# loadCell_Amplifier_v0_01.net
KiCad netlist of a schematic drawn in EAGLE
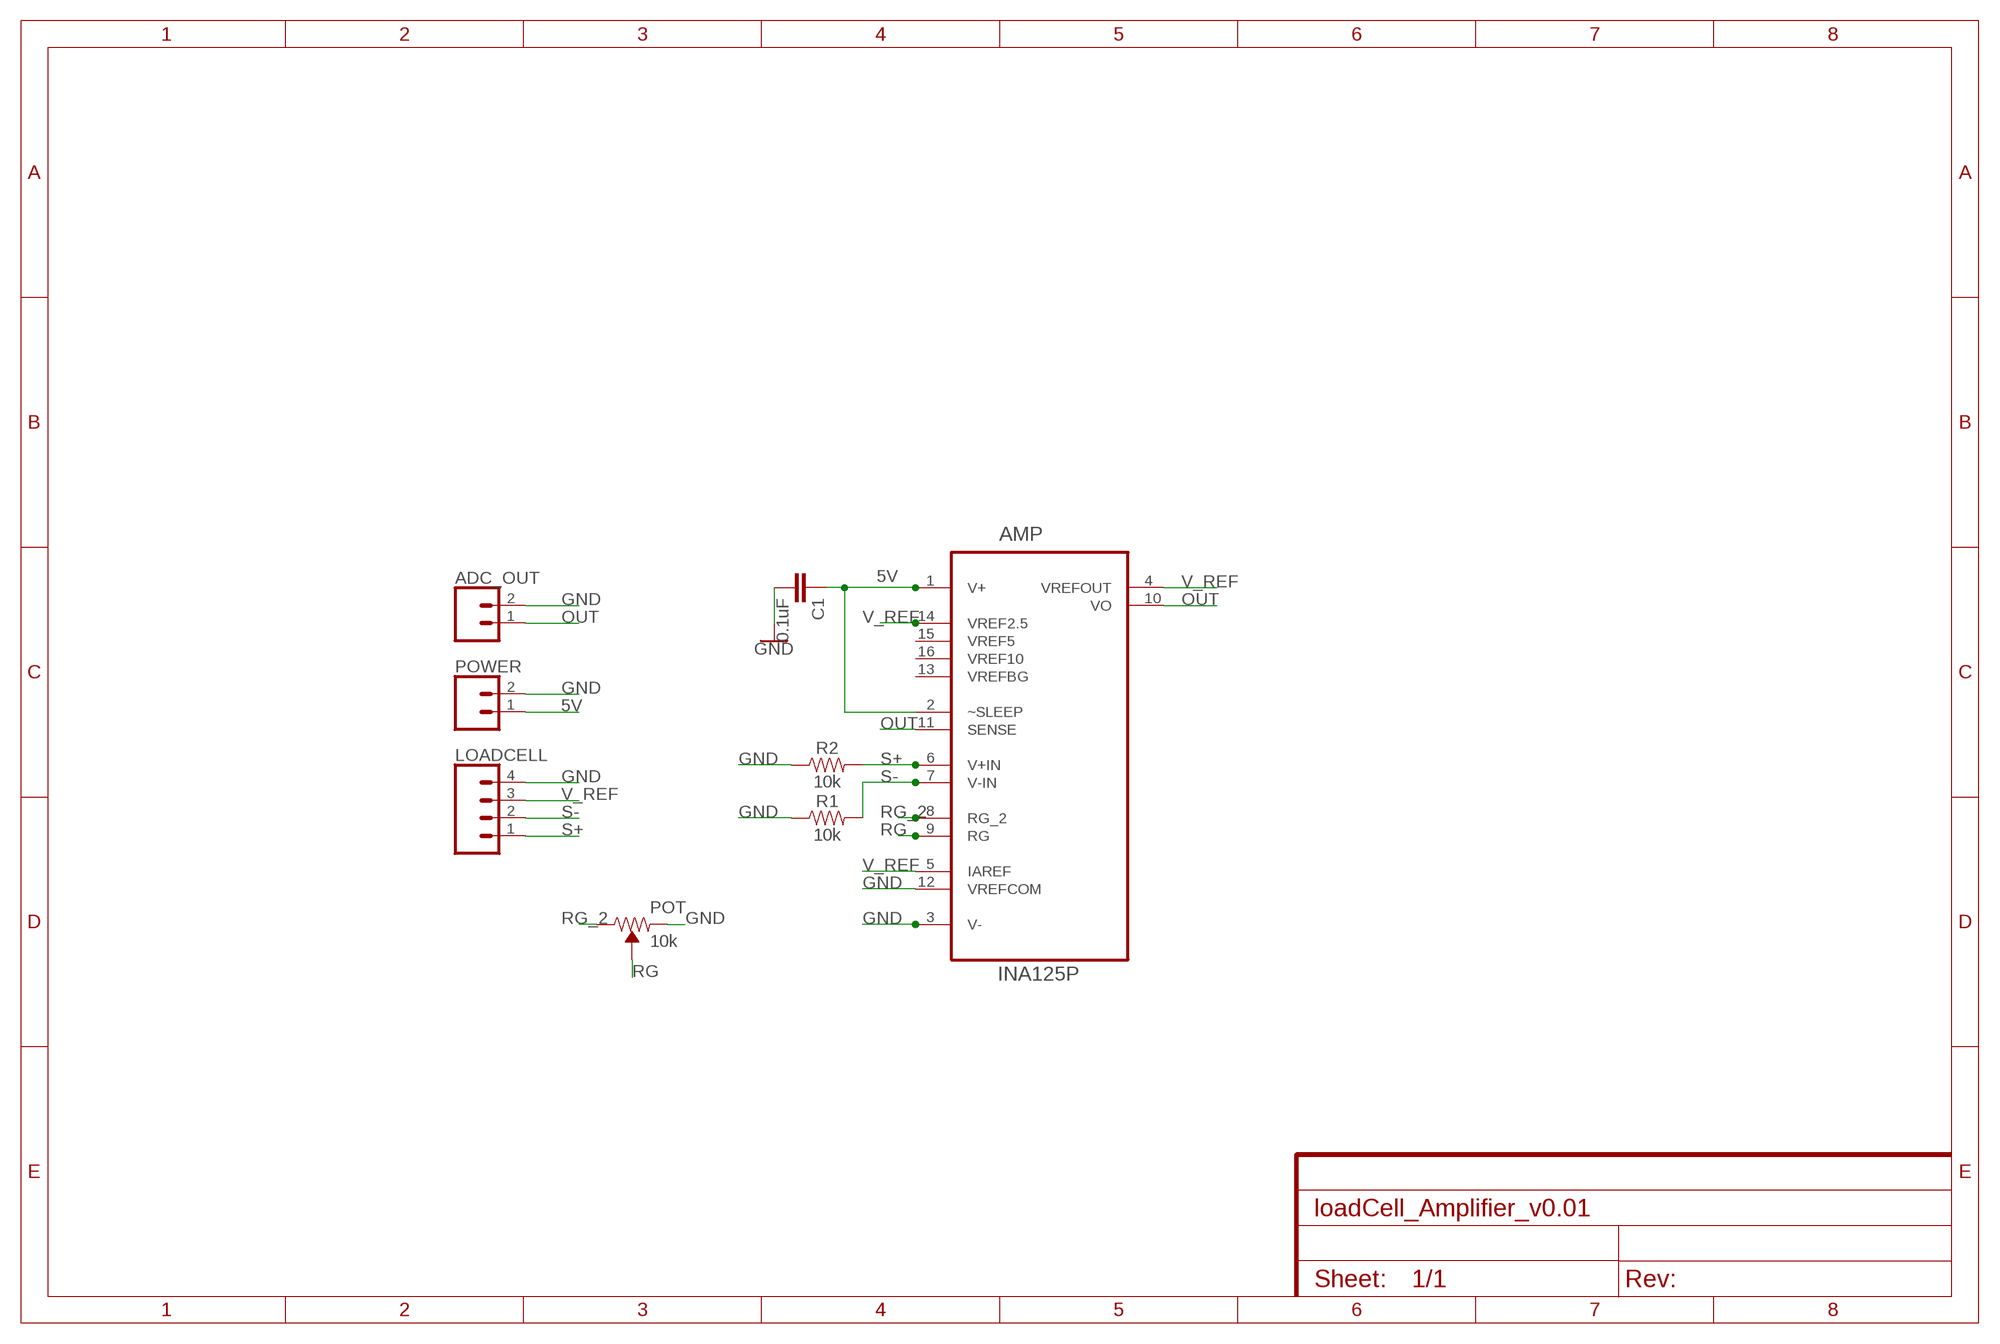
[diagram p0: schematic, sheet 1]

(export (version "E")
  (design (tool "Eeschema 10.0.6"))
  (components
    (comp (ref "ADC_OUT")
      (value "CONN_02")
      (footprint "eagle-import:1X02")
      (libsource (lib "eagle-import") (part "CONN_02"))
    )
    (comp (ref "AMP")
      (value "INA125P")
      (footprint "eagle-import:DIP254P762X508-16")
      (libsource (lib "eagle-import") (part "INA125P"))
    )
    (comp (ref "C1")
      (value "0.1uF")
      (footprint "eagle-import:CAP-PTH-SMALL-KIT")
      (libsource (lib "eagle-import") (part "0.1UF-KIT-EZ-50V-20%"))
    )
    (comp (ref "LOADCELL")
      (value "CONN_04")
      (footprint "eagle-import:1X04")
      (libsource (lib "eagle-import") (part "CONN_04"))
    )
    (comp (ref "POT")
      (value "10k")
      (footprint "eagle-import:TRIMPOT-PTH-3386U")
      (libsource (lib "eagle-import") (part "TRIMPOT-PTH-10MM-KNOB-1/2W-10%"))
    )
    (comp (ref "POWER")
      (value "CONN_02")
      (footprint "eagle-import:1X02")
      (libsource (lib "eagle-import") (part "CONN_02"))
    )
    (comp (ref "R1")
      (value "10k")
      (footprint "eagle-import:AXIAL-0.3")
      (libsource (lib "eagle-import") (part "10KOHM-HORIZ-1/4W-1%"))
    )
    (comp (ref "R2")
      (value "10k")
      (footprint "eagle-import:AXIAL-0.3")
      (libsource (lib "eagle-import") (part "10KOHM-HORIZ-1/4W-1%"))
    )
  )
  (nets
    (net (code "1") (name "/5V") (class "Default")
      (node (ref "AMP") (pin "1") (pinfunction "V+_1") (pintype "power_in"))
      (node (ref "AMP") (pin "2") (pinfunction "~{SLEEP}_2") (pintype "passive"))
      (node (ref "C1") (pin "1") (pinfunction "1_1") (pintype "passive"))
      (node (ref "POWER") (pin "1") (pinfunction "1_1") (pintype "passive"))
    )
    (net (code "2") (name "/OUT") (class "Default")
      (node (ref "ADC_OUT") (pin "1") (pinfunction "1_1") (pintype "passive"))
      (node (ref "AMP") (pin "10") (pinfunction "VO_10") (pintype "output"))
      (node (ref "AMP") (pin "11") (pinfunction "SENSE_11") (pintype "input"))
    )
    (net (code "3") (name "/RG") (class "Default")
      (node (ref "AMP") (pin "9") (pinfunction "RG_9") (pintype "passive"))
      (node (ref "POT") (pin "2") (pinfunction "WIPER_2") (pintype "passive"))
    )
    (net (code "4") (name "/RG_2") (class "Default")
      (node (ref "AMP") (pin "8") (pinfunction "RG_2_8") (pintype "passive"))
      (node (ref "POT") (pin "3") (pinfunction "CW_3") (pintype "passive"))
    )
    (net (code "5") (name "/S+") (class "Default")
      (node (ref "AMP") (pin "6") (pinfunction "V+IN_6") (pintype "power_in"))
      (node (ref "LOADCELL") (pin "1") (pinfunction "1_1") (pintype "passive"))
      (node (ref "R2") (pin "P$2") (pinfunction "2_P$2") (pintype "passive"))
    )
    (net (code "6") (name "/S-") (class "Default")
      (node (ref "AMP") (pin "7") (pinfunction "V-IN_7") (pintype "power_in"))
      (node (ref "LOADCELL") (pin "2") (pinfunction "2_2") (pintype "passive"))
      (node (ref "R1") (pin "P$2") (pinfunction "2_P$2") (pintype "passive"))
    )
    (net (code "7") (name "/VREF5") (class "Default")
      (node (ref "AMP") (pin "15") (pinfunction "VREF5_15") (pintype "power_in"))
    )
    (net (code "8") (name "/VREF10") (class "Default")
      (node (ref "AMP") (pin "16") (pinfunction "VREF10_16") (pintype "power_in"))
    )
    (net (code "9") (name "/VREFBG") (class "Default")
      (node (ref "AMP") (pin "13") (pinfunction "VREFBG_13") (pintype "power_in"))
    )
    (net (code "10") (name "/V_REF") (class "Default")
      (node (ref "AMP") (pin "14") (pinfunction "VREF2.5_14") (pintype "power_in"))
      (node (ref "AMP") (pin "4") (pinfunction "VREFOUT_4") (pintype "output"))
      (node (ref "AMP") (pin "5") (pinfunction "IAREF_5") (pintype "passive"))
      (node (ref "LOADCELL") (pin "3") (pinfunction "3_3") (pintype "passive"))
    )
    (net (code "11") (name "GND") (class "Default")
      (node (ref "ADC_OUT") (pin "2") (pinfunction "2_2") (pintype "passive"))
      (node (ref "AMP") (pin "12") (pinfunction "VREFCOM_12") (pintype "passive"))
      (node (ref "AMP") (pin "3") (pinfunction "V-_3") (pintype "power_in"))
      (node (ref "C1") (pin "2") (pinfunction "2_2") (pintype "passive"))
      (node (ref "LOADCELL") (pin "4") (pinfunction "4_4") (pintype "passive"))
      (node (ref "POT") (pin "1") (pinfunction "CCW_1") (pintype "passive"))
      (node (ref "POWER") (pin "2") (pinfunction "2_2") (pintype "passive"))
      (node (ref "R1") (pin "P$1") (pinfunction "1_P$1") (pintype "passive"))
      (node (ref "R2") (pin "P$1") (pinfunction "1_P$1") (pintype "passive"))
    )
  )
)
